# DC-DC-Brick.net
KiCad netlist of a schematic drawn in EAGLE
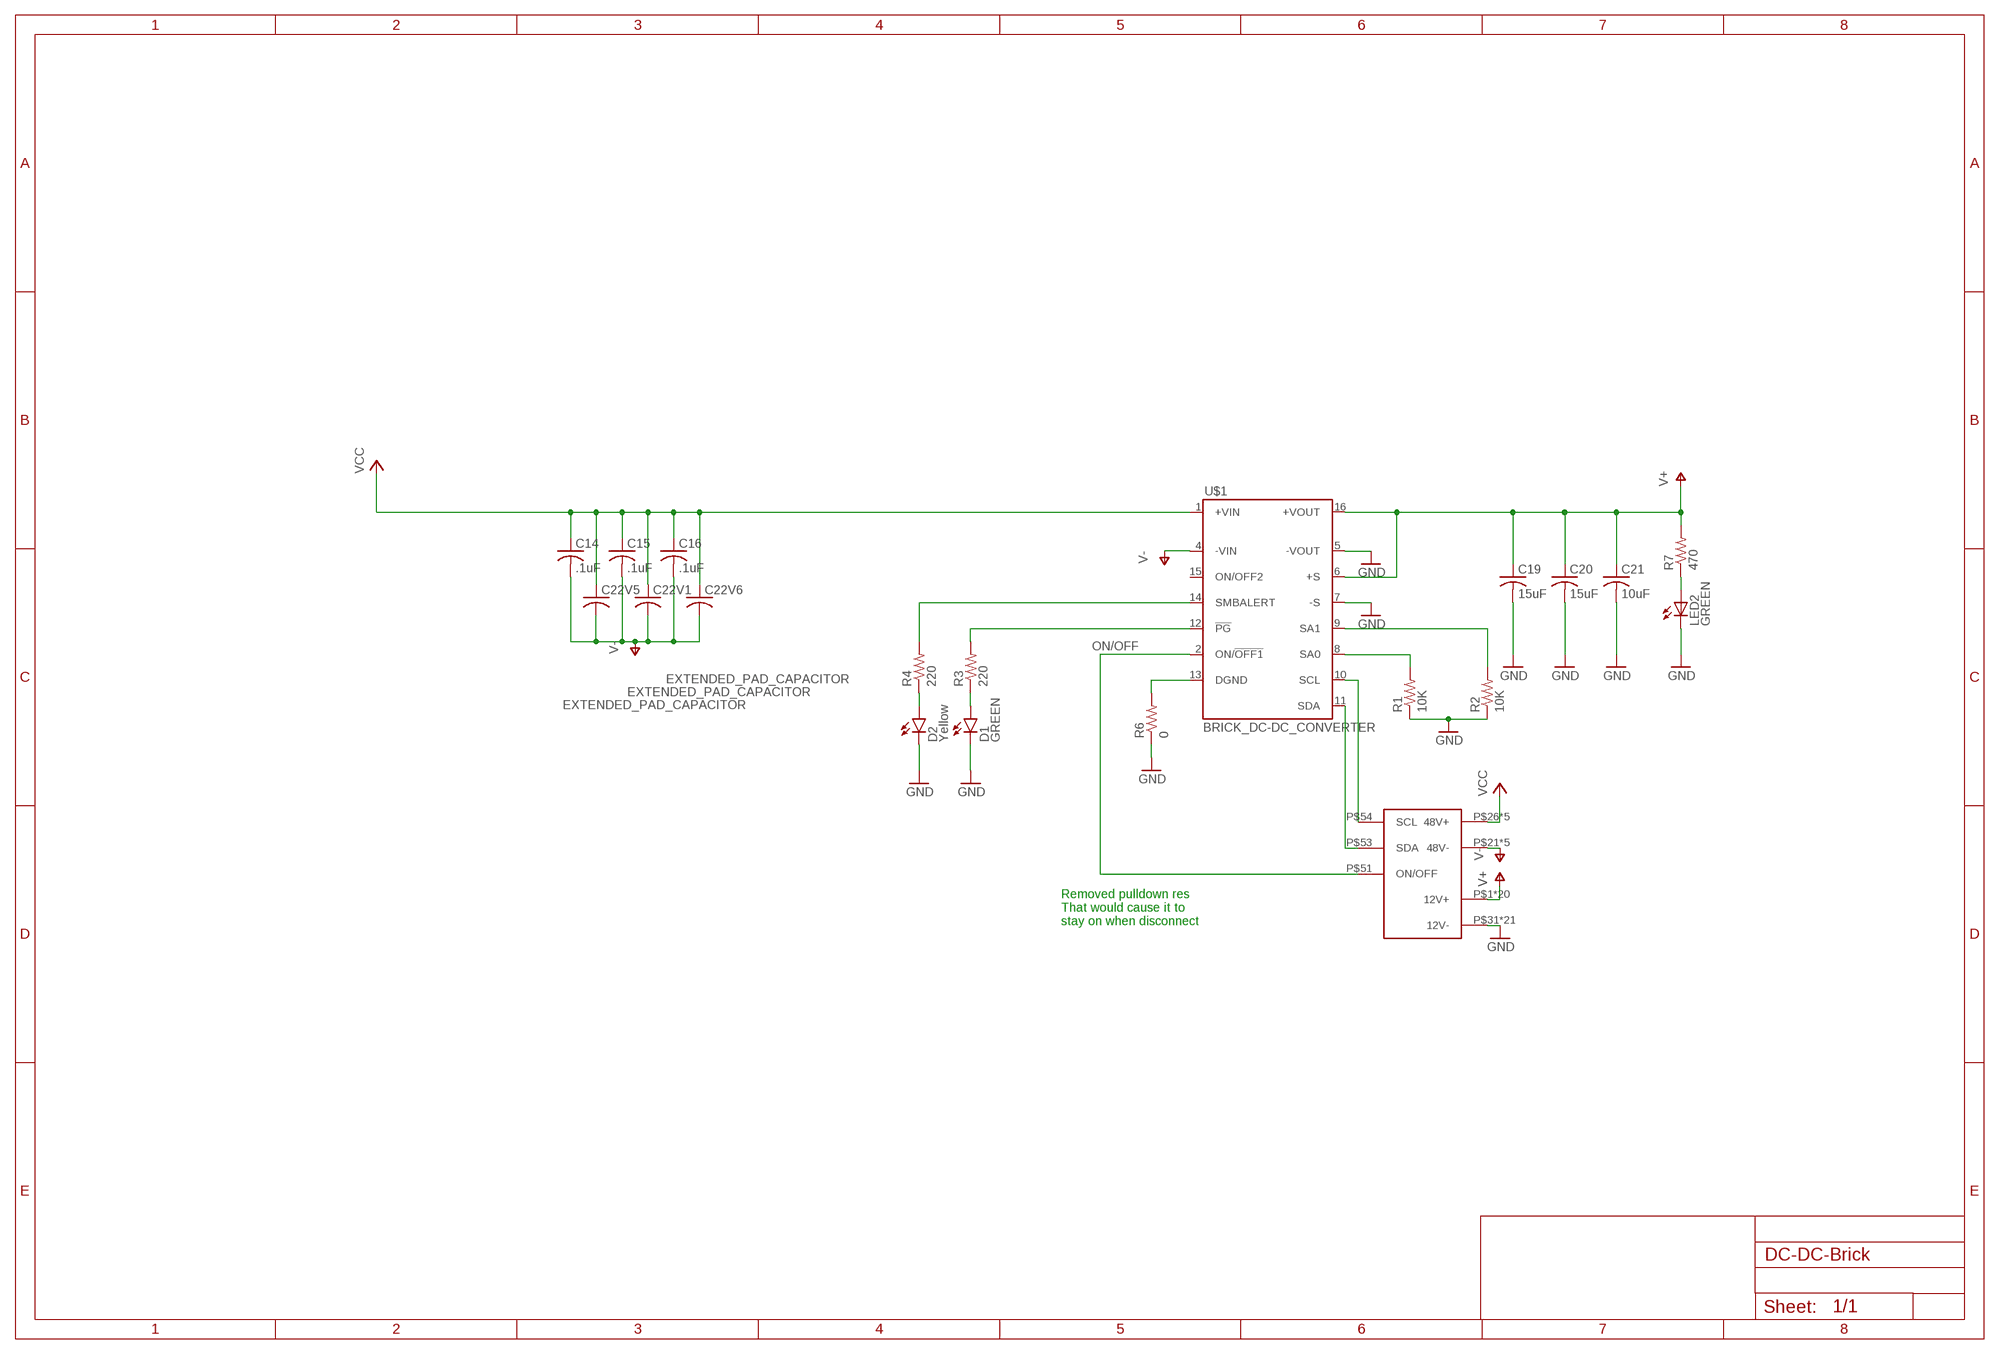
[diagram p0: schematic, sheet 1]

(export (version "E")
  (design (tool "Eeschema 10.0.6"))
  (components
    (comp (ref "C14")
      (value ".1uF")
      (footprint "eagle-import:C0603")
      (libsource (lib "eagle-import") (part "C-USC0603"))
    )
    (comp (ref "C15")
      (value ".1uF")
      (footprint "eagle-import:C0603")
      (libsource (lib "eagle-import") (part "C-USC0603"))
    )
    (comp (ref "C16")
      (value ".1uF")
      (footprint "eagle-import:C0603")
      (libsource (lib "eagle-import") (part "C-USC0603"))
    )
    (comp (ref "C19")
      (value "15uF")
      (footprint "eagle-import:C3216")
      (libsource (lib "eagle-import") (part "C-USC3216"))
    )
    (comp (ref "C20")
      (value "15uF")
      (footprint "eagle-import:C3216")
      (libsource (lib "eagle-import") (part "C-USC3216"))
    )
    (comp (ref "C21")
      (value "10uF")
      (footprint "eagle-import:C0603")
      (libsource (lib "eagle-import") (part "C-USC0603"))
    )
    (comp (ref "C22V1")
      (value "EXTENDED_PAD_CAPACITOR")
      (footprint "eagle-import:MODIFIED-NICHICON-UX-8X10")
      (libsource (lib "eagle-import") (part "EXTENDED_PAD_CAPACITOR"))
    )
    (comp (ref "C22V5")
      (value "EXTENDED_PAD_CAPACITOR")
      (footprint "eagle-import:MODIFIED-NICHICON-UX-8X10")
      (libsource (lib "eagle-import") (part "EXTENDED_PAD_CAPACITOR"))
    )
    (comp (ref "C22V6")
      (value "EXTENDED_PAD_CAPACITOR")
      (footprint "eagle-import:MODIFIED-NICHICON-UX-8X10")
      (libsource (lib "eagle-import") (part "EXTENDED_PAD_CAPACITOR"))
    )
    (comp (ref "D1")
      (value "GREEN")
      (footprint "eagle-import:LED-0603")
      (libsource (lib "eagle-import") (part "LED-GREEN0603"))
    )
    (comp (ref "D2")
      (value "Yellow")
      (footprint "eagle-import:LED-0603")
      (libsource (lib "eagle-import") (part "LED-YELLOW0603"))
    )
    (comp (ref "LED2")
      (value "GREEN")
      (footprint "eagle-import:LED-0603")
      (fields (field (name "PARTNO") "160-1446-1-ND"))
      (libsource (lib "eagle-import") (part "LED0603"))
    )
    (comp (ref "R1")
      (value "10K")
      (footprint "eagle-import:0603-RES")
      (libsource (lib "eagle-import") (part "10KOHM-1/10W-1%(0603)0603"))
    )
    (comp (ref "R2")
      (value "10K")
      (footprint "eagle-import:0603-RES")
      (libsource (lib "eagle-import") (part "10KOHM-1/10W-1%(0603)0603"))
    )
    (comp (ref "R3")
      (value "220")
      (footprint "eagle-import:0603-RES")
      (libsource (lib "eagle-import") (part "1KOHM-1/10W-1%(0603)"))
    )
    (comp (ref "R4")
      (value "220")
      (footprint "eagle-import:0603-RES")
      (libsource (lib "eagle-import") (part "1KOHM-1/10W-1%(0603)"))
    )
    (comp (ref "R6")
      (value "0")
      (footprint "eagle-import:0603-RES")
      (libsource (lib "eagle-import") (part "1KOHM-1/10W-1%(0603)"))
    )
    (comp (ref "R7")
      (value "470")
      (footprint "eagle-import:0603-RES")
      (libsource (lib "eagle-import") (part "470OHM1/10W1%(0603)"))
    )
    (comp (ref "U$1")
      (value "BRICK_DC-DC_CONVERTER")
      (footprint "eagle-import:BRICK_DC-DC_CONVERTER")
      (libsource (lib "eagle-import") (part "BRICK_DC-DC_CONVERTER"))
    )
    (comp (ref "U$3")
      (value "POWER-BRICK-CONNECTOR")
      (footprint "eagle-import:POWER-BRICK-CONNECTOR")
      (libsource (lib "eagle-import") (part "POWER-BRICK-CONNECTOR"))
    )
  )
  (nets
    (net (code "1") (name "/ON{slash}OFF") (class "Default")
      (node (ref "U$1") (pin "2") (pinfunction "ON/~{OFF1}_2") (pintype "bidirectional"))
      (node (ref "U$3") (pin "P$51") (pinfunction "ON/OFF_P$51") (pintype "bidirectional"))
    )
    (net (code "2") (name "GND") (class "Default")
      (node (ref "C19") (pin "2") (pinfunction "2_2") (pintype "passive"))
      (node (ref "C20") (pin "2") (pinfunction "2_2") (pintype "passive"))
      (node (ref "C21") (pin "2") (pinfunction "2_2") (pintype "passive"))
      (node (ref "D1") (pin "C") (pinfunction "C_C") (pintype "passive"))
      (node (ref "D2") (pin "C") (pinfunction "C_C") (pintype "passive"))
      (node (ref "LED2") (pin "C") (pinfunction "C_C") (pintype "passive"))
      (node (ref "R1") (pin "1") (pinfunction "1_1") (pintype "passive"))
      (node (ref "R2") (pin "1") (pinfunction "1_1") (pintype "passive"))
      (node (ref "R6") (pin "1") (pinfunction "1_1") (pintype "passive"))
      (node (ref "U$1") (pin "5") (pinfunction "-VOUT_5") (pintype "power_in"))
      (node (ref "U$1") (pin "7") (pinfunction "-S_7") (pintype "bidirectional"))
      (node (ref "U$3") (pin "P$31") (pinfunction "12V-_P$31") (pintype "bidirectional"))
      (node (ref "U$3") (pin "P$32") (pinfunction "12V-_P$32") (pintype "bidirectional"))
      (node (ref "U$3") (pin "P$33") (pinfunction "12V-_P$33") (pintype "bidirectional"))
      (node (ref "U$3") (pin "P$34") (pinfunction "12V-_P$34") (pintype "bidirectional"))
      (node (ref "U$3") (pin "P$35") (pinfunction "12V-_P$35") (pintype "bidirectional"))
      (node (ref "U$3") (pin "P$36") (pinfunction "12V-_P$36") (pintype "bidirectional"))
      (node (ref "U$3") (pin "P$37") (pinfunction "12V-_P$37") (pintype "bidirectional"))
      (node (ref "U$3") (pin "P$38") (pinfunction "12V-_P$38") (pintype "bidirectional"))
      (node (ref "U$3") (pin "P$39") (pinfunction "12V-_P$39") (pintype "bidirectional"))
      (node (ref "U$3") (pin "P$40") (pinfunction "12V-_P$40") (pintype "bidirectional"))
      (node (ref "U$3") (pin "P$41") (pinfunction "12V-_P$41") (pintype "bidirectional"))
      (node (ref "U$3") (pin "P$42") (pinfunction "12V-_P$42") (pintype "bidirectional"))
      (node (ref "U$3") (pin "P$43") (pinfunction "12V-_P$43") (pintype "bidirectional"))
      (node (ref "U$3") (pin "P$44") (pinfunction "12V-_P$44") (pintype "bidirectional"))
      (node (ref "U$3") (pin "P$45") (pinfunction "12V-_P$45") (pintype "bidirectional"))
      (node (ref "U$3") (pin "P$46") (pinfunction "12V-_P$46") (pintype "bidirectional"))
      (node (ref "U$3") (pin "P$47") (pinfunction "12V-_P$47") (pintype "bidirectional"))
      (node (ref "U$3") (pin "P$48") (pinfunction "12V-_P$48") (pintype "bidirectional"))
      (node (ref "U$3") (pin "P$49") (pinfunction "12V-_P$49") (pintype "bidirectional"))
      (node (ref "U$3") (pin "P$50") (pinfunction "12V-_P$50") (pintype "bidirectional"))
      (node (ref "U$3") (pin "P$52") (pinfunction "12V-_P$52") (pintype "bidirectional"))
    )
    (net (code "3") (name "Net-(D1-PadA)") (class "Default")
      (node (ref "D1") (pin "A") (pinfunction "A_A") (pintype "passive"))
      (node (ref "R3") (pin "1") (pinfunction "1_1") (pintype "passive"))
    )
    (net (code "4") (name "Net-(D2-PadA)") (class "Default")
      (node (ref "D2") (pin "A") (pinfunction "A_A") (pintype "passive"))
      (node (ref "R4") (pin "1") (pinfunction "1_1") (pintype "passive"))
    )
    (net (code "5") (name "Net-(LED2-PadA)") (class "Default")
      (node (ref "LED2") (pin "A") (pinfunction "A_A") (pintype "passive"))
      (node (ref "R7") (pin "1") (pinfunction "1_1") (pintype "passive"))
    )
    (net (code "6") (name "Net-(U$1-DGND)") (class "Default")
      (node (ref "R6") (pin "2") (pinfunction "2_2") (pintype "passive"))
      (node (ref "U$1") (pin "13") (pinfunction "DGND_13") (pintype "power_in"))
    )
    (net (code "7") (name "Net-(U$1-SA0)") (class "Default")
      (node (ref "R1") (pin "2") (pinfunction "2_2") (pintype "passive"))
      (node (ref "U$1") (pin "8") (pinfunction "SA0_8") (pintype "bidirectional"))
    )
    (net (code "8") (name "Net-(U$1-SA1)") (class "Default")
      (node (ref "R2") (pin "2") (pinfunction "2_2") (pintype "passive"))
      (node (ref "U$1") (pin "9") (pinfunction "SA1_9") (pintype "bidirectional"))
    )
    (net (code "9") (name "Net-(U$1-SCL)") (class "Default")
      (node (ref "U$1") (pin "10") (pinfunction "SCL_10") (pintype "bidirectional"))
      (node (ref "U$3") (pin "P$54") (pinfunction "SCL_P$54") (pintype "bidirectional"))
    )
    (net (code "10") (name "Net-(U$1-SDA)") (class "Default")
      (node (ref "U$1") (pin "11") (pinfunction "SDA_11") (pintype "bidirectional"))
      (node (ref "U$3") (pin "P$53") (pinfunction "SDA_P$53") (pintype "bidirectional"))
    )
    (net (code "11") (name "Net-(U$1-SMBALERT)") (class "Default")
      (node (ref "R4") (pin "2") (pinfunction "2_2") (pintype "passive"))
      (node (ref "U$1") (pin "14") (pinfunction "SMBALERT_14") (pintype "bidirectional"))
    )
    (net (code "12") (name "Net-(U$1-~{PG})") (class "Default")
      (node (ref "R3") (pin "2") (pinfunction "2_2") (pintype "passive"))
      (node (ref "U$1") (pin "12") (pinfunction "~{PG}_12") (pintype "bidirectional"))
    )
    (net (code "13") (name "V+") (class "Default")
      (node (ref "C19") (pin "1") (pinfunction "1_1") (pintype "passive"))
      (node (ref "C20") (pin "1") (pinfunction "1_1") (pintype "passive"))
      (node (ref "C21") (pin "1") (pinfunction "1_1") (pintype "passive"))
      (node (ref "R7") (pin "2") (pinfunction "2_2") (pintype "passive"))
      (node (ref "U$1") (pin "16") (pinfunction "+VOUT_16") (pintype "power_in"))
      (node (ref "U$1") (pin "6") (pinfunction "+S_6") (pintype "bidirectional"))
      (node (ref "U$3") (pin "P$1") (pinfunction "12V+_P$1") (pintype "bidirectional"))
      (node (ref "U$3") (pin "P$10") (pinfunction "12V+_P$10") (pintype "bidirectional"))
      (node (ref "U$3") (pin "P$11") (pinfunction "12V+_P$11") (pintype "bidirectional"))
      (node (ref "U$3") (pin "P$12") (pinfunction "12V+_P$12") (pintype "bidirectional"))
      (node (ref "U$3") (pin "P$13") (pinfunction "12V+_P$13") (pintype "bidirectional"))
      (node (ref "U$3") (pin "P$14") (pinfunction "12V+_P$14") (pintype "bidirectional"))
      (node (ref "U$3") (pin "P$15") (pinfunction "12V+_P$15") (pintype "bidirectional"))
      (node (ref "U$3") (pin "P$16") (pinfunction "12V+_P$16") (pintype "bidirectional"))
      (node (ref "U$3") (pin "P$17") (pinfunction "12V+_P$17") (pintype "bidirectional"))
      (node (ref "U$3") (pin "P$18") (pinfunction "12V+_P$18") (pintype "bidirectional"))
      (node (ref "U$3") (pin "P$19") (pinfunction "12V+_P$19") (pintype "bidirectional"))
      (node (ref "U$3") (pin "P$2") (pinfunction "12V+_P$2") (pintype "bidirectional"))
      (node (ref "U$3") (pin "P$20") (pinfunction "12V+_P$20") (pintype "bidirectional"))
      (node (ref "U$3") (pin "P$3") (pinfunction "12V+_P$3") (pintype "bidirectional"))
      (node (ref "U$3") (pin "P$4") (pinfunction "12V+_P$4") (pintype "bidirectional"))
      (node (ref "U$3") (pin "P$5") (pinfunction "12V+_P$5") (pintype "bidirectional"))
      (node (ref "U$3") (pin "P$6") (pinfunction "12V+_P$6") (pintype "bidirectional"))
      (node (ref "U$3") (pin "P$7") (pinfunction "12V+_P$7") (pintype "bidirectional"))
      (node (ref "U$3") (pin "P$8") (pinfunction "12V+_P$8") (pintype "bidirectional"))
      (node (ref "U$3") (pin "P$9") (pinfunction "12V+_P$9") (pintype "bidirectional"))
    )
    (net (code "14") (name "V-") (class "Default")
      (node (ref "C14") (pin "2") (pinfunction "2_2") (pintype "passive"))
      (node (ref "C15") (pin "2") (pinfunction "2_2") (pintype "passive"))
      (node (ref "C16") (pin "2") (pinfunction "2_2") (pintype "passive"))
      (node (ref "C22V1") (pin "P$1") (pinfunction "4_P$1") (pintype "passive"))
      (node (ref "C22V5") (pin "P$1") (pinfunction "4_P$1") (pintype "passive"))
      (node (ref "C22V6") (pin "P$1") (pinfunction "4_P$1") (pintype "passive"))
      (node (ref "U$1") (pin "4") (pinfunction "-VIN_4") (pintype "power_in"))
      (node (ref "U$3") (pin "P$21") (pinfunction "48V-_P$21") (pintype "bidirectional"))
      (node (ref "U$3") (pin "P$22") (pinfunction "48V-_P$22") (pintype "bidirectional"))
      (node (ref "U$3") (pin "P$23") (pinfunction "48V-_P$23") (pintype "bidirectional"))
      (node (ref "U$3") (pin "P$24") (pinfunction "48V-_P$24") (pintype "bidirectional"))
      (node (ref "U$3") (pin "P$25") (pinfunction "48V-_P$25") (pintype "bidirectional"))
    )
    (net (code "15") (name "VCC") (class "Default")
      (node (ref "C14") (pin "1") (pinfunction "1_1") (pintype "passive"))
      (node (ref "C15") (pin "1") (pinfunction "1_1") (pintype "passive"))
      (node (ref "C16") (pin "1") (pinfunction "1_1") (pintype "passive"))
      (node (ref "C22V1") (pin "P$3") (pinfunction "3_P$3") (pintype "passive"))
      (node (ref "C22V5") (pin "P$3") (pinfunction "3_P$3") (pintype "passive"))
      (node (ref "C22V6") (pin "P$3") (pinfunction "3_P$3") (pintype "passive"))
      (node (ref "U$1") (pin "1") (pinfunction "+VIN_1") (pintype "power_in"))
      (node (ref "U$3") (pin "P$26") (pinfunction "48V+_P$26") (pintype "bidirectional"))
      (node (ref "U$3") (pin "P$27") (pinfunction "48V+_P$27") (pintype "bidirectional"))
      (node (ref "U$3") (pin "P$28") (pinfunction "48V+_P$28") (pintype "bidirectional"))
      (node (ref "U$3") (pin "P$29") (pinfunction "48V+_P$29") (pintype "bidirectional"))
      (node (ref "U$3") (pin "P$30") (pinfunction "48V+_P$30") (pintype "bidirectional"))
    )
    (net (code "16") (name "unconnected-(U$1-ON{slash}OFF2-Pad15)") (class "Default")
      (node (ref "U$1") (pin "15") (pinfunction "ON/OFF2_15") (pintype "bidirectional"))
    )
  )
)
